# Light_Monitoring.net
KiCad netlist of a schematic drawn in Altium Designer
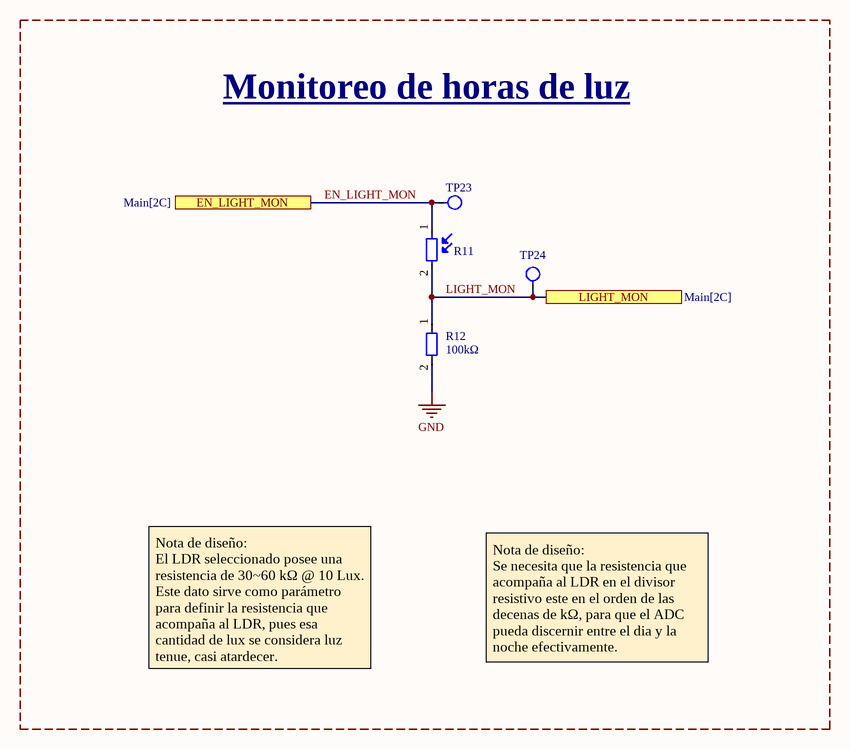
[diagram p0: Light_Monitoring.SchDoc]

(export (version "E")
  (design (tool "Eeschema 10.0.6"))
  (components
    (comp (ref "R11")
      (value "LDR")
      (footprint "Generic LDR")
      (description "LDR for sensing daylight hours.")
      (libsource (lib "Sensors") (part "Generic LDR"))
    )
    (comp (ref "R12")
      (value "100kΩ")
      (footprint "RES_0603")
      (description "RES  100k 1% 0603")
      (fields (field (name "Comment") "100k"))
      (libsource (lib "Passive_Components") (part "Generic R"))
    )
    (comp (ref "TP23")
      (value "Testpoint SMD")
      (footprint "Testpoint_SMD")
      (description "Testpoint SMD de 1mm de diametro.")
      (libsource (lib "Connectors") (part "Testpoint_SMD"))
    )
    (comp (ref "TP24")
      (value "Testpoint SMD")
      (footprint "Testpoint_SMD")
      (description "Testpoint SMD de 1mm de diametro.")
      (libsource (lib "Connectors") (part "Testpoint_SMD"))
    )
  )
  (nets
    (net (code "1") (name "/EN_LIGHT_MON") (class "Default")
      (node (ref "R11") (pin "1") (pinfunction "1_1") (pintype "passive"))
      (node (ref "TP23") (pin "1") (pinfunction "1_1") (pintype "passive"))
    )
    (net (code "2") (name "/LIGHT_MON") (class "Default")
      (node (ref "R11") (pin "2") (pinfunction "2_2") (pintype "passive"))
      (node (ref "R12") (pin "1") (pinfunction "1_1") (pintype "passive"))
      (node (ref "TP24") (pin "1") (pinfunction "1_1") (pintype "passive"))
    )
    (net (code "3") (name "GND") (class "Default")
      (node (ref "R12") (pin "2") (pinfunction "2_2") (pintype "passive"))
    )
  )
)
